# BLE.net
KiCad netlist of a schematic drawn in Altium Designer
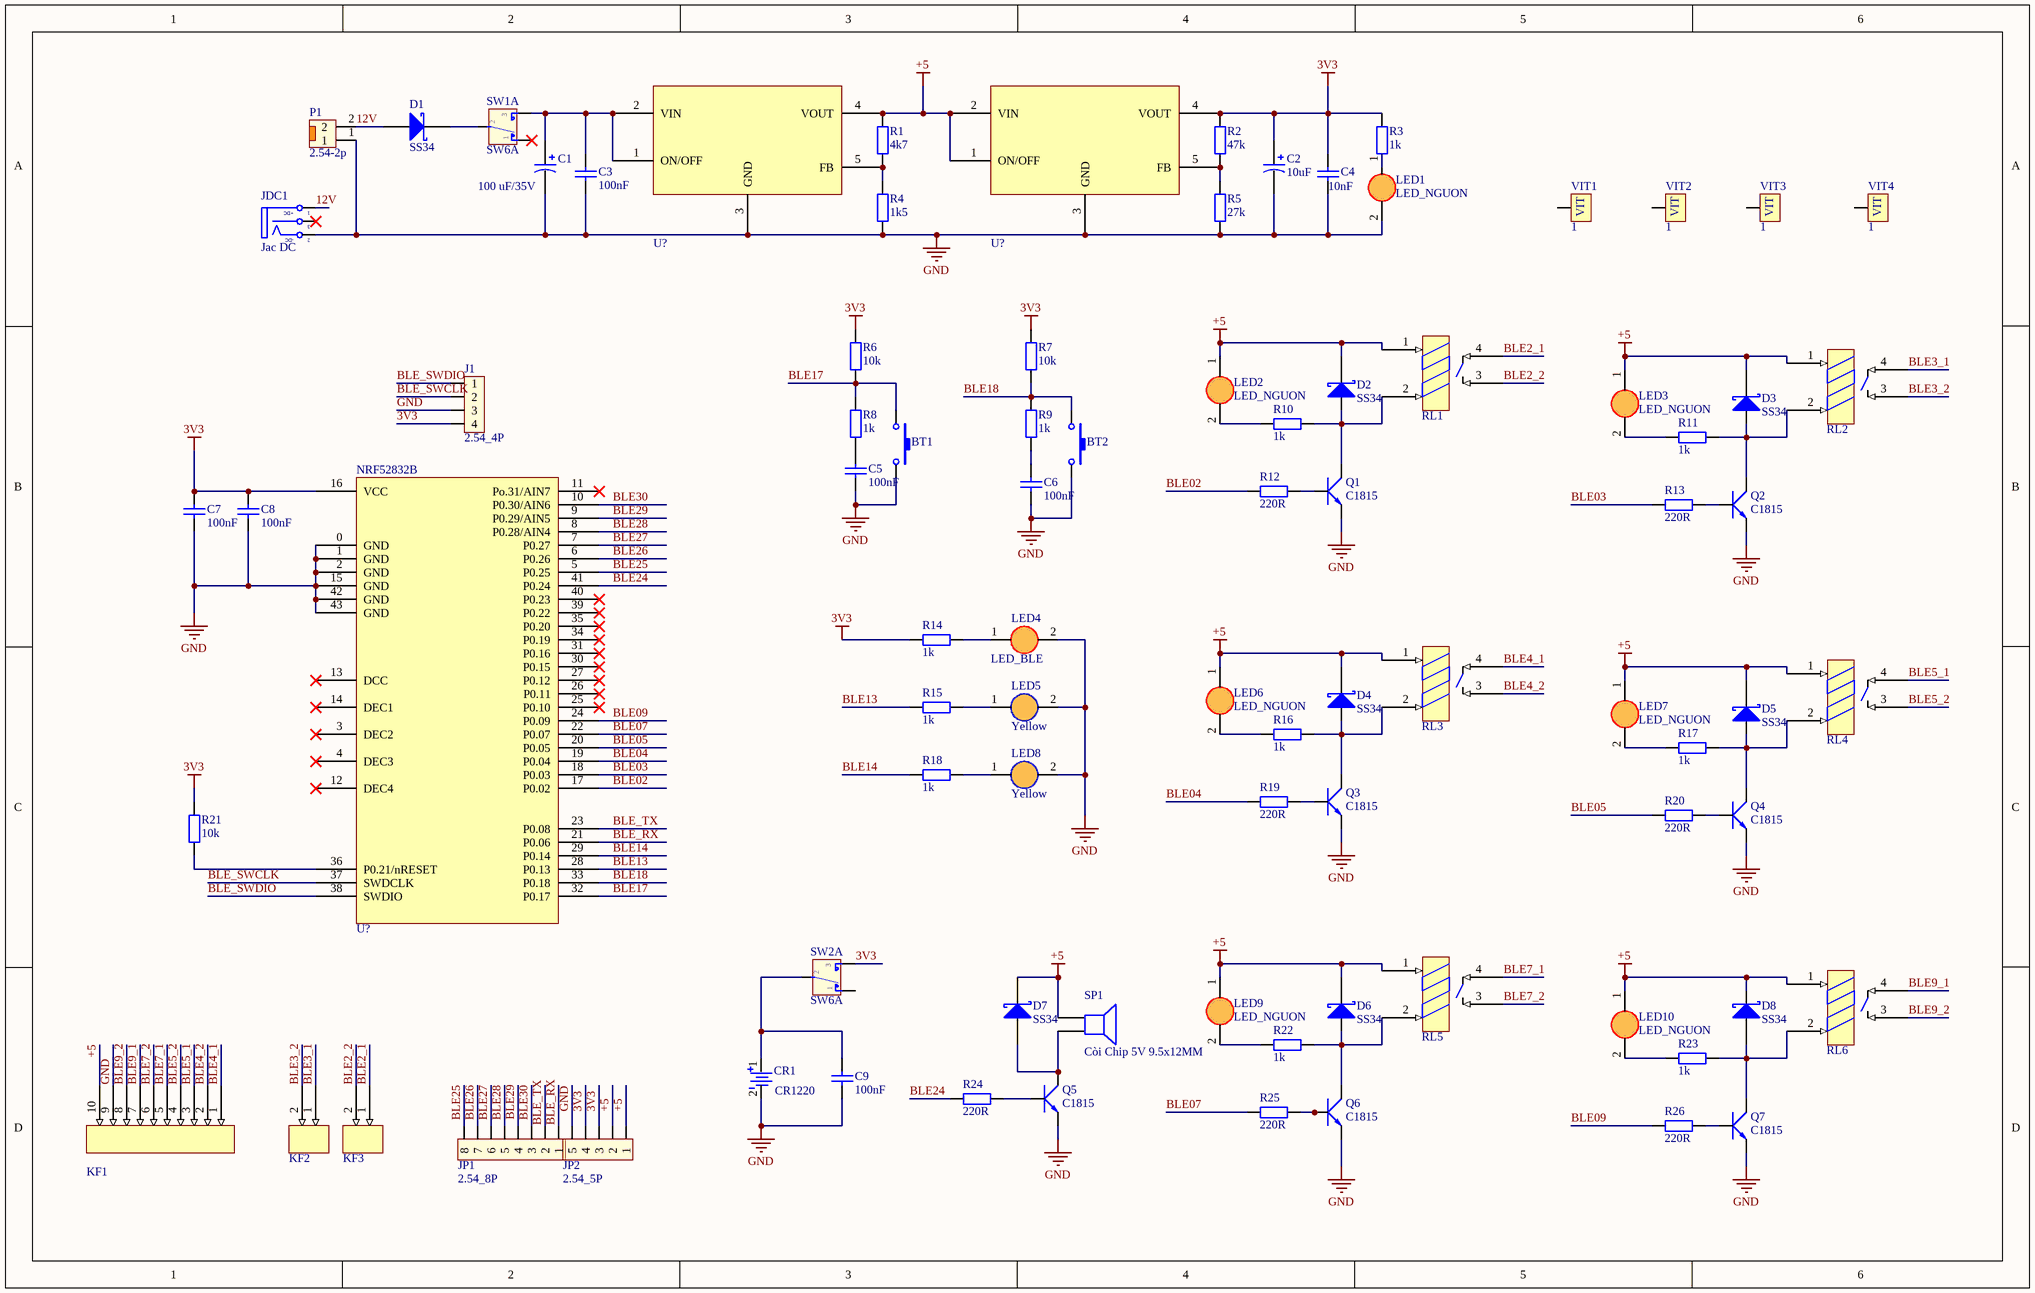
[diagram p0: BLE.SchDoc]

(export (version "E")
  (design (tool "Eeschema 10.0.6"))
  (components
    (comp (ref "BT1")
      (value "Nút Nhấn 2 Chân 3x6x2.5MM SMD")
      (footprint "Nut Nhan 2 Chan SMD_N")
      (description "Dán")
      (libsource (lib "NhomLib (1)") (part "Nut Nhan 2 Chan SMD"))
    )
    (comp (ref "BT2")
      (value "Nút Nhấn 2 Chân 3x6x2.5MM SMD")
      (footprint "Nut Nhan 2 Chan SMD_N")
      (description "Dán")
      (libsource (lib "NhomLib (1)") (part "Nut Nhan 2 Chan SMD"))
    )
    (comp (ref "C1")
      (value "100 uF/35V")
      (footprint "CAP_ALUM_SMD_100102_TYPE_G")
      (description "CAP ALUM 330uF 20% 35V SMD")
      (fields (field (name "MPN") "EEE-FK1C331P") (field (name "MFR") "Panasonic"))
      (libsource (lib "NhomLib (1)") (part "EEE-FK1C331P"))
    )
    (comp (ref "C2")
      (value "10uF")
      (footprint "CAP_ALUM_SMD_5054_TYPE_C")
      (description "CAP ALUM 33uF 20% 16V SMD")
      (fields (field (name "MPN") "EEE-FK1C330P") (field (name "MFR") "Panasonic"))
      (libsource (lib "NhomLib (1)") (part "EEE-FK1C330P"))
    )
    (comp (ref "C3")
      (value "100nF")
      (footprint "tu 0805")
      (description "Dán")
      (libsource (lib "NhomLib (1)") (part "Tu 0805 6.8nF 50V 10%"))
    )
    (comp (ref "C4")
      (value "10nF")
      (footprint "tu 0805")
      (description "Dán")
      (libsource (lib "NhomLib (1)") (part "Tu 0805 6.8nF 50V 10%"))
    )
    (comp (ref "C5")
      (value "100nF")
      (footprint "tu 0805")
      (description "Dán")
      (libsource (lib "NhomLib (1)") (part "Tu 0805 6.8nF 50V 10%"))
    )
    (comp (ref "C6")
      (value "100nF")
      (footprint "tu 0805")
      (description "Dán")
      (libsource (lib "NhomLib (1)") (part "Tu 0805 6.8nF 50V 10%"))
    )
    (comp (ref "C7")
      (value "100nF")
      (footprint "tu 0805")
      (description "Dán")
      (libsource (lib "NhomLib (1)") (part "Tu 0805 6.8nF 50V 10%"))
    )
    (comp (ref "C8")
      (value "100nF")
      (footprint "tu 0805")
      (description "Dán")
      (libsource (lib "NhomLib (1)") (part "Tu 0805 6.8nF 50V 10%"))
    )
    (comp (ref "C9")
      (value "100nF")
      (footprint "tu 0805")
      (description "Dán")
      (libsource (lib "NhomLib (1)") (part "Tu 0805 6.8nF 50V 10%"))
    )
    (comp (ref "CR1")
      (value "CR1220")
      (footprint "CR1220_HOLDER_SMD")
      (libsource (lib "VINH TRI") (part "CR1220"))
    )
    (comp (ref "D1")
      (value "SS34")
      (footprint "DIODE_DO214AC_SMA")
      (description "DIODE SCHOTTKY 40V 3A SMA")
      (libsource (lib "NhomLib (1)") (part "SS34"))
    )
    (comp (ref "D2")
      (value "SS34")
      (footprint "DIODE_DO214AC_SMA")
      (description "DIODE SCHOTTKY 40V 3A SMA")
      (libsource (lib "NhomLib (1)") (part "SS34"))
    )
    (comp (ref "D3")
      (value "SS34")
      (footprint "DIODE_DO214AC_SMA")
      (description "DIODE SCHOTTKY 40V 3A SMA")
      (libsource (lib "NhomLib (1)") (part "SS34"))
    )
    (comp (ref "D4")
      (value "SS34")
      (footprint "DIODE_DO214AC_SMA")
      (description "DIODE SCHOTTKY 40V 3A SMA")
      (libsource (lib "NhomLib (1)") (part "SS34"))
    )
    (comp (ref "D5")
      (value "SS34")
      (footprint "DIODE_DO214AC_SMA")
      (description "DIODE SCHOTTKY 40V 3A SMA")
      (libsource (lib "NhomLib (1)") (part "SS34"))
    )
    (comp (ref "D6")
      (value "SS34")
      (footprint "DIODE_DO214AC_SMA")
      (description "DIODE SCHOTTKY 40V 3A SMA")
      (libsource (lib "NhomLib (1)") (part "SS34"))
    )
    (comp (ref "D7")
      (value "SS34")
      (footprint "DIODE_DO214AC_SMA")
      (description "DIODE SCHOTTKY 40V 3A SMA")
      (libsource (lib "NhomLib (1)") (part "SS34"))
    )
    (comp (ref "D8")
      (value "SS34")
      (footprint "DIODE_DO214AC_SMA")
      (description "DIODE SCHOTTKY 40V 3A SMA")
      (libsource (lib "NhomLib (1)") (part "SS34"))
    )
    (comp (ref "J1")
      (value "2.54_4P")
      (footprint "jump don duc thang 2.54_4p")
      (description "Cắm")
      (libsource (lib "NhomLib (1)") (part "Jump Don Duc Thang 2.54_4P"))
    )
    (comp (ref "JDC1")
      (value "Jac DC")
      (footprint "DC-IN")
      (description "Jac DC input")
      (libsource (lib "NhomLib (1)") (part "DCIN"))
    )
    (comp (ref "JP1")
      (value "2.54_8P")
      (footprint "Jump Don Duc Thang 2.54_8p")
      (description "Cắm")
      (libsource (lib "NhomLib (1)") (part "Jump Don Duc 2.54_8P"))
    )
    (comp (ref "JP2")
      (value "2.54_5P")
      (footprint "jump don duc 2.54_5p")
      (description "Cắm")
      (libsource (lib "NhomLib (1)") (part "Jump Don Duc 2.54_5P"))
    )
    (comp (ref "KF1")
      (value "KF142R-10")
      (footprint "KF10")
      (description "KF142R-10P-5.08mm")
      (libsource (lib "B212H_01") (part "KF10"))
    )
    (comp (ref "KF2")
      (value "~")
      (footprint "KF2")
      (description "KF142R-2 5.08mm")
      (libsource (lib "B212H_01") (part "KF2"))
    )
    (comp (ref "KF3")
      (value "~")
      (footprint "KF2")
      (description "KF142R-2 5.08mm")
      (libsource (lib "B212H_01") (part "KF2"))
    )
    (comp (ref "LED1")
      (value "LED_NGUON")
      (footprint "led 0805")
      (description "Dán")
      (libsource (lib "NhomLib (1)") (part "Led 0805 Do"))
    )
    (comp (ref "LED2")
      (value "LED_NGUON")
      (footprint "led 0805")
      (description "Dán")
      (libsource (lib "NhomLib (1)") (part "Led 0805 Do"))
    )
    (comp (ref "LED3")
      (value "LED_NGUON")
      (footprint "led 0805")
      (description "Dán")
      (libsource (lib "NhomLib (1)") (part "Led 0805 Do"))
    )
    (comp (ref "LED4")
      (value "LED_BLE")
      (footprint "led 0805")
      (description "Dán")
      (libsource (lib "NhomLib (1)") (part "Led 0805 Do"))
    )
    (comp (ref "LED5")
      (value "Yellow")
      (footprint "led 0805")
      (description "Dán")
      (libsource (lib "NhomLib (1)") (part "Led 0805 Xanh Duong"))
    )
    (comp (ref "LED6")
      (value "LED_NGUON")
      (footprint "led 0805")
      (description "Dán")
      (libsource (lib "NhomLib (1)") (part "Led 0805 Do"))
    )
    (comp (ref "LED7")
      (value "LED_NGUON")
      (footprint "led 0805")
      (description "Dán")
      (libsource (lib "NhomLib (1)") (part "Led 0805 Do"))
    )
    (comp (ref "LED8")
      (value "Yellow")
      (footprint "led 0805")
      (description "Dán")
      (libsource (lib "NhomLib (1)") (part "Led 0805 Xanh Duong"))
    )
    (comp (ref "LED9")
      (value "LED_NGUON")
      (footprint "led 0805")
      (description "Dán")
      (libsource (lib "NhomLib (1)") (part "Led 0805 Do"))
    )
    (comp (ref "LED10")
      (value "LED_NGUON")
      (footprint "led 0805")
      (description "Dán")
      (libsource (lib "NhomLib (1)") (part "Led 0805 Do"))
    )
    (comp (ref "MIC1")
      (value "U?")
      (footprint "Mic5V")
      (description "3A")
      (libsource (lib "NodeMCU-ESP8266") (part "Mic5V"))
    )
    (comp (ref "MIC2")
      (value "U?")
      (footprint "Mic5V")
      (description "3A")
      (libsource (lib "NodeMCU-ESP8266") (part "Mic5V"))
    )
    (comp (ref "NRF52832") (value "U?") (footprint "NRF52832") (libsource (lib "NRF52832") (part "U?")))
    (comp (ref "P1")
      (value "2.54-2p")
      (footprint "Header Duc Thang 2P 2.54")
      (description "Cắm")
      (libsource (lib "NhomLib (1)") (part "Header 2.54-2p Duc Thang"))
    )
    (comp (ref "Q1")
      (value "C1815")
      (footprint "SOT23B")
      (description "NPN 600mW, ECB")
      (libsource (lib "syhaunguyen") (part "C1815"))
    )
    (comp (ref "Q2")
      (value "C1815")
      (footprint "SOT23B")
      (description "NPN 600mW, ECB")
      (libsource (lib "syhaunguyen") (part "C1815"))
    )
    (comp (ref "Q3")
      (value "C1815")
      (footprint "SOT23B")
      (description "NPN 600mW, ECB")
      (libsource (lib "syhaunguyen") (part "C1815"))
    )
    (comp (ref "Q4")
      (value "C1815")
      (footprint "SOT23B")
      (description "NPN 600mW, ECB")
      (libsource (lib "syhaunguyen") (part "C1815"))
    )
    (comp (ref "Q5")
      (value "C1815")
      (footprint "SOT23B")
      (description "NPN 600mW, ECB")
      (libsource (lib "syhaunguyen") (part "C1815"))
    )
    (comp (ref "Q6")
      (value "C1815")
      (footprint "SOT23B")
      (description "NPN 600mW, ECB")
      (libsource (lib "syhaunguyen") (part "C1815"))
    )
    (comp (ref "Q7")
      (value "C1815")
      (footprint "SOT23B")
      (description "NPN 600mW, ECB")
      (libsource (lib "syhaunguyen") (part "C1815"))
    )
    (comp (ref "R1")
      (value "4k7")
      (footprint "tro 0805")
      (description "Dán")
      (libsource (lib "NhomLib (1)") (part "Tro 0805 1% 10k"))
    )
    (comp (ref "R2")
      (value "47k")
      (footprint "tro 0805")
      (description "Dán")
      (libsource (lib "NhomLib (1)") (part "Tro 0805 1% 10k"))
    )
    (comp (ref "R3")
      (value "1k")
      (footprint "tro 0805")
      (description "Dán")
      (libsource (lib "NhomLib (1)") (part "Tro 0805 1% 10k"))
    )
    (comp (ref "R4")
      (value "1k5")
      (footprint "tro 0805")
      (description "Dán")
      (libsource (lib "NhomLib (1)") (part "Tro 0805 1% 10k"))
    )
    (comp (ref "R5")
      (value "27k")
      (footprint "tro 0805")
      (description "Dán")
      (libsource (lib "NhomLib (1)") (part "Tro 0805 1% 10k"))
    )
    (comp (ref "R6")
      (value "10k")
      (footprint "tro 0805")
      (description "Dán")
      (libsource (lib "NhomLib (1)") (part "Tro 0805 1% 10k"))
    )
    (comp (ref "R7")
      (value "10k")
      (footprint "tro 0805")
      (description "Dán")
      (libsource (lib "NhomLib (1)") (part "Tro 0805 1% 10k"))
    )
    (comp (ref "R8")
      (value "1k")
      (footprint "tro 0805")
      (description "Dán")
      (libsource (lib "NhomLib (1)") (part "Tro 0805 1% 10k"))
    )
    (comp (ref "R9")
      (value "1k")
      (footprint "tro 0805")
      (description "Dán")
      (libsource (lib "NhomLib (1)") (part "Tro 0805 1% 10k"))
    )
    (comp (ref "R10")
      (value "1k")
      (footprint "tro 0805")
      (description "Dán")
      (libsource (lib "NhomLib (1)") (part "Tro 0805 1% 10k"))
    )
    (comp (ref "R11")
      (value "1k")
      (footprint "tro 0805")
      (description "Dán")
      (libsource (lib "NhomLib (1)") (part "Tro 0805 1% 10k"))
    )
    (comp (ref "R12")
      (value "220R")
      (footprint "tro 0805")
      (description "Dán")
      (libsource (lib "NhomLib (1)") (part "Tro 0805 1% 10k"))
    )
    (comp (ref "R13")
      (value "220R")
      (footprint "tro 0805")
      (description "Dán")
      (libsource (lib "NhomLib (1)") (part "Tro 0805 1% 10k"))
    )
    (comp (ref "R14")
      (value "1k")
      (footprint "tro 0805")
      (description "Dán")
      (libsource (lib "NhomLib (1)") (part "Tro 0805 1% 10k"))
    )
    (comp (ref "R15")
      (value "1k")
      (footprint "tro 0805")
      (description "Dán")
      (libsource (lib "NhomLib (1)") (part "Tro 0805 1% 10k"))
    )
    (comp (ref "R16")
      (value "1k")
      (footprint "tro 0805")
      (description "Dán")
      (libsource (lib "NhomLib (1)") (part "Tro 0805 1% 10k"))
    )
    (comp (ref "R17")
      (value "1k")
      (footprint "tro 0805")
      (description "Dán")
      (libsource (lib "NhomLib (1)") (part "Tro 0805 1% 10k"))
    )
    (comp (ref "R18")
      (value "1k")
      (footprint "tro 0805")
      (description "Dán")
      (libsource (lib "NhomLib (1)") (part "Tro 0805 1% 10k"))
    )
    (comp (ref "R19")
      (value "220R")
      (footprint "tro 0805")
      (description "Dán")
      (libsource (lib "NhomLib (1)") (part "Tro 0805 1% 10k"))
    )
    (comp (ref "R20")
      (value "220R")
      (footprint "tro 0805")
      (description "Dán")
      (libsource (lib "NhomLib (1)") (part "Tro 0805 1% 10k"))
    )
    (comp (ref "R21")
      (value "10k")
      (footprint "tro 0805")
      (description "Dán")
      (libsource (lib "NhomLib (1)") (part "Tro 0805 1% 10k"))
    )
    (comp (ref "R22")
      (value "1k")
      (footprint "tro 0805")
      (description "Dán")
      (libsource (lib "NhomLib (1)") (part "Tro 0805 1% 10k"))
    )
    (comp (ref "R23")
      (value "1k")
      (footprint "tro 0805")
      (description "Dán")
      (libsource (lib "NhomLib (1)") (part "Tro 0805 1% 10k"))
    )
    (comp (ref "R24")
      (value "220R")
      (footprint "tro 0805")
      (description "Dán")
      (libsource (lib "NhomLib (1)") (part "Tro 0805 1% 10k"))
    )
    (comp (ref "R25")
      (value "220R")
      (footprint "tro 0805")
      (description "Dán")
      (libsource (lib "NhomLib (1)") (part "Tro 0805 1% 10k"))
    )
    (comp (ref "R26")
      (value "220R")
      (footprint "tro 0805")
      (description "Dán")
      (libsource (lib "NhomLib (1)") (part "Tro 0805 1% 10k"))
    )
    (comp (ref "RL1") (value "Relay-4") (footprint "Relay-4") (libsource (lib "B212H_01") (part "Relay-4")))
    (comp (ref "RL2") (value "Relay-4") (footprint "Relay-4") (libsource (lib "B212H_01") (part "Relay-4")))
    (comp (ref "RL3") (value "Relay-4") (footprint "Relay-4") (libsource (lib "B212H_01") (part "Relay-4")))
    (comp (ref "RL4") (value "Relay-4") (footprint "Relay-4") (libsource (lib "B212H_01") (part "Relay-4")))
    (comp (ref "RL5") (value "Relay-4") (footprint "Relay-4") (libsource (lib "B212H_01") (part "Relay-4")))
    (comp (ref "RL6") (value "Relay-4") (footprint "Relay-4") (libsource (lib "B212H_01") (part "Relay-4")))
    (comp (ref "SP1")
      (value "Còi Chip 5V 9.5x12MM")
      (footprint "SPEAKER")
      (description "Cắm")
      (libsource (lib "NhomLib (1)") (part "Coi Chip 5V"))
    )
    (comp (ref "SW1")
      (value "SW6A")
      (footprint "SW6")
      (description "SW-DTDP - 6 Pin")
      (libsource (lib "NhomLib (1)") (part "SW6A"))
    )
    (comp (ref "SW2")
      (value "SW6A")
      (footprint "SW6")
      (description "SW-DTDP - 6 Pin")
      (libsource (lib "NhomLib (1)") (part "SW6A"))
    )
    (comp (ref "VIT1")
      (value "1")
      (footprint "VIT")
      (description "Oc Vit")
      (libsource (lib "NhomLib (1)") (part "VIT"))
    )
    (comp (ref "VIT2")
      (value "1")
      (footprint "VIT")
      (description "Oc Vit")
      (libsource (lib "NhomLib (1)") (part "VIT"))
    )
    (comp (ref "VIT3")
      (value "1")
      (footprint "VIT")
      (description "Oc Vit")
      (libsource (lib "NhomLib (1)") (part "VIT"))
    )
    (comp (ref "VIT4")
      (value "1")
      (footprint "VIT")
      (description "Oc Vit")
      (libsource (lib "NhomLib (1)") (part "VIT"))
    )
  )
  (nets
    (net (code "1") (name "+5") (class "Default")
      (node (ref "D2") (pin "2") (pinfunction "K_2") (pintype "passive"))
      (node (ref "D3") (pin "2") (pinfunction "K_2") (pintype "passive"))
      (node (ref "D4") (pin "2") (pinfunction "K_2") (pintype "passive"))
      (node (ref "D5") (pin "2") (pinfunction "K_2") (pintype "passive"))
      (node (ref "D6") (pin "2") (pinfunction "K_2") (pintype "passive"))
      (node (ref "D7") (pin "2") (pinfunction "K_2") (pintype "passive"))
      (node (ref "D8") (pin "2") (pinfunction "K_2") (pintype "passive"))
      (node (ref "JP2") (pin "1") (pinfunction "1_1") (pintype "passive"))
      (node (ref "JP2") (pin "2") (pinfunction "2_2") (pintype "passive"))
      (node (ref "KF1") (pin "10") (pintype "input"))
      (node (ref "LED10") (pin "1") (pinfunction "A_1") (pintype "passive"))
      (node (ref "LED2") (pin "1") (pinfunction "A_1") (pintype "passive"))
      (node (ref "LED3") (pin "1") (pinfunction "A_1") (pintype "passive"))
      (node (ref "LED6") (pin "1") (pinfunction "A_1") (pintype "passive"))
      (node (ref "LED7") (pin "1") (pinfunction "A_1") (pintype "passive"))
      (node (ref "LED9") (pin "1") (pinfunction "A_1") (pintype "passive"))
      (node (ref "MIC1") (pin "4") (pinfunction "VOUT_4") (pintype "passive"))
      (node (ref "MIC2") (pin "1") (pinfunction "ON/OFF_1") (pintype "passive"))
      (node (ref "MIC2") (pin "2") (pinfunction "VIN_2") (pintype "passive"))
      (node (ref "R1") (pin "1") (pinfunction "1_1") (pintype "passive"))
      (node (ref "RL1") (pin "1") (pintype "input"))
      (node (ref "RL2") (pin "1") (pintype "input"))
      (node (ref "RL3") (pin "1") (pintype "input"))
      (node (ref "RL4") (pin "1") (pintype "input"))
      (node (ref "RL5") (pin "1") (pintype "input"))
      (node (ref "RL6") (pin "1") (pintype "input"))
      (node (ref "SP1") (pin "1") (pinfunction "1_1") (pintype "passive"))
    )
    (net (code "2") (name "/12V") (class "Default")
      (node (ref "D1") (pin "1") (pinfunction "A_1") (pintype "passive"))
      (node (ref "JDC1") (pin "1") (pinfunction "T_1") (pintype "passive"))
      (node (ref "P1") (pin "2") (pinfunction "2_2") (pintype "passive"))
    )
    (net (code "3") (name "/BLE02") (class "Default")
      (node (ref "NRF52832") (pin "17") (pinfunction "P0.02_17") (pintype "passive"))
      (node (ref "R12") (pin "2") (pinfunction "2_2") (pintype "passive"))
    )
    (net (code "4") (name "/BLE2_1") (class "Default")
      (node (ref "KF3") (pin "1") (pintype "input"))
      (node (ref "RL1") (pin "4") (pintype "input"))
    )
    (net (code "5") (name "/BLE2_2") (class "Default")
      (node (ref "KF3") (pin "2") (pintype "input"))
      (node (ref "RL1") (pin "3") (pintype "input"))
    )
    (net (code "6") (name "/BLE03") (class "Default")
      (node (ref "NRF52832") (pin "18") (pinfunction "P0.03_18") (pintype "passive"))
      (node (ref "R13") (pin "2") (pinfunction "2_2") (pintype "passive"))
    )
    (net (code "7") (name "/BLE3_1") (class "Default")
      (node (ref "KF2") (pin "1") (pintype "input"))
      (node (ref "RL2") (pin "4") (pintype "input"))
    )
    (net (code "8") (name "/BLE3_2") (class "Default")
      (node (ref "KF2") (pin "2") (pintype "input"))
      (node (ref "RL2") (pin "3") (pintype "input"))
    )
    (net (code "9") (name "/BLE04") (class "Default")
      (node (ref "NRF52832") (pin "19") (pinfunction "P0.04_19") (pintype "passive"))
      (node (ref "R19") (pin "2") (pinfunction "2_2") (pintype "passive"))
    )
    (net (code "10") (name "/BLE4_1") (class "Default")
      (node (ref "KF1") (pin "1") (pintype "input"))
      (node (ref "RL3") (pin "4") (pintype "input"))
    )
    (net (code "11") (name "/BLE4_2") (class "Default")
      (node (ref "KF1") (pin "2") (pintype "input"))
      (node (ref "RL3") (pin "3") (pintype "input"))
    )
    (net (code "12") (name "/BLE05") (class "Default")
      (node (ref "NRF52832") (pin "20") (pinfunction "P0.05_20") (pintype "passive"))
      (node (ref "R20") (pin "2") (pinfunction "2_2") (pintype "passive"))
    )
    (net (code "13") (name "/BLE5_1") (class "Default")
      (node (ref "KF1") (pin "3") (pintype "input"))
      (node (ref "RL4") (pin "4") (pintype "input"))
    )
    (net (code "14") (name "/BLE5_2") (class "Default")
      (node (ref "KF1") (pin "4") (pintype "input"))
      (node (ref "RL4") (pin "3") (pintype "input"))
    )
    (net (code "15") (name "/BLE07") (class "Default")
      (node (ref "NRF52832") (pin "22") (pinfunction "P0.07_22") (pintype "passive"))
      (node (ref "R25") (pin "2") (pinfunction "2_2") (pintype "passive"))
    )
    (net (code "16") (name "/BLE7_1") (class "Default")
      (node (ref "KF1") (pin "5") (pintype "input"))
      (node (ref "RL5") (pin "4") (pintype "input"))
    )
    (net (code "17") (name "/BLE7_2") (class "Default")
      (node (ref "KF1") (pin "6") (pintype "input"))
      (node (ref "RL5") (pin "3") (pintype "input"))
    )
    (net (code "18") (name "/BLE09") (class "Default")
      (node (ref "NRF52832") (pin "24") (pinfunction "P0.09_24") (pintype "passive"))
      (node (ref "R26") (pin "2") (pinfunction "2_2") (pintype "passive"))
    )
    (net (code "19") (name "/BLE9_1") (class "Default")
      (node (ref "KF1") (pin "7") (pintype "input"))
      (node (ref "RL6") (pin "4") (pintype "input"))
    )
    (net (code "20") (name "/BLE9_2") (class "Default")
      (node (ref "KF1") (pin "8") (pintype "input"))
      (node (ref "RL6") (pin "3") (pintype "input"))
    )
    (net (code "21") (name "/BLE13") (class "Default")
      (node (ref "NRF52832") (pin "28") (pinfunction "P0.13_28") (pintype "passive"))
      (node (ref "R15") (pin "2") (pinfunction "2_2") (pintype "passive"))
    )
    (net (code "22") (name "/BLE14") (class "Default")
      (node (ref "NRF52832") (pin "29") (pinfunction "P0.14_29") (pintype "passive"))
      (node (ref "R18") (pin "2") (pinfunction "2_2") (pintype "passive"))
    )
    (net (code "23") (name "/BLE17") (class "Default")
      (node (ref "BT1") (pin "1") (pinfunction "1_1") (pintype "passive"))
      (node (ref "NRF52832") (pin "32") (pinfunction "P0.17_32") (pintype "passive"))
      (node (ref "R6") (pin "2") (pinfunction "2_2") (pintype "passive"))
      (node (ref "R8") (pin "2") (pinfunction "2_2") (pintype "passive"))
    )
    (net (code "24") (name "/BLE18") (class "Default")
      (node (ref "BT2") (pin "1") (pinfunction "1_1") (pintype "passive"))
      (node (ref "NRF52832") (pin "33") (pinfunction "P0.18_33") (pintype "passive"))
      (node (ref "R7") (pin "2") (pinfunction "2_2") (pintype "passive"))
      (node (ref "R9") (pin "2") (pinfunction "2_2") (pintype "passive"))
    )
    (net (code "25") (name "/BLE24") (class "Default")
      (node (ref "NRF52832") (pin "41") (pinfunction "P0.24_41") (pintype "passive"))
      (node (ref "R24") (pin "2") (pinfunction "2_2") (pintype "passive"))
    )
    (net (code "26") (name "/BLE25") (class "Default")
      (node (ref "JP1") (pin "8") (pinfunction "8_8") (pintype "passive"))
      (node (ref "NRF52832") (pin "5") (pinfunction "P0.25_5") (pintype "passive"))
    )
    (net (code "27") (name "/BLE26") (class "Default")
      (node (ref "JP1") (pin "7") (pinfunction "7_7") (pintype "passive"))
      (node (ref "NRF52832") (pin "6") (pinfunction "P0.26_6") (pintype "passive"))
    )
    (net (code "28") (name "/BLE27") (class "Default")
      (node (ref "JP1") (pin "6") (pinfunction "6_6") (pintype "passive"))
      (node (ref "NRF52832") (pin "7") (pinfunction "P0.27_7") (pintype "passive"))
    )
    (net (code "29") (name "/BLE28") (class "Default")
      (node (ref "JP1") (pin "5") (pinfunction "5_5") (pintype "passive"))
      (node (ref "NRF52832") (pin "8") (pinfunction "P0.28/AIN4_8") (pintype "passive"))
    )
    (net (code "30") (name "/BLE29") (class "Default")
      (node (ref "JP1") (pin "4") (pinfunction "4_4") (pintype "passive"))
      (node (ref "NRF52832") (pin "9") (pinfunction "P0.29/AIN5_9") (pintype "passive"))
    )
    (net (code "31") (name "/BLE30") (class "Default")
      (node (ref "JP1") (pin "3") (pinfunction "3_3") (pintype "passive"))
      (node (ref "NRF52832") (pin "10") (pinfunction "P0.30/AIN6_10") (pintype "passive"))
    )
    (net (code "32") (name "/BLE_RX") (class "Default")
      (node (ref "JP1") (pin "1") (pinfunction "1_1") (pintype "passive"))
      (node (ref "NRF52832") (pin "21") (pinfunction "P0.06_21") (pintype "passive"))
    )
    (net (code "33") (name "/BLE_SWCLK") (class "Default")
      (node (ref "J1") (pin "2") (pinfunction "2_2") (pintype "passive"))
      (node (ref "NRF52832") (pin "37") (pinfunction "SWDCLK_37") (pintype "passive"))
    )
    (net (code "34") (name "/BLE_SWDIO") (class "Default")
      (node (ref "J1") (pin "1") (pinfunction "1_1") (pintype "passive"))
      (node (ref "NRF52832") (pin "38") (pinfunction "SWDIO_38") (pintype "passive"))
    )
    (net (code "35") (name "/BLE_TX") (class "Default")
      (node (ref "JP1") (pin "2") (pinfunction "2_2") (pintype "passive"))
      (node (ref "NRF52832") (pin "23") (pinfunction "P0.08_23") (pintype "passive"))
    )
    (net (code "36") (name "3V3") (class "Default")
      (node (ref "C2") (pin "1") (pinfunction "1_1") (pintype "passive"))
      (node (ref "C4") (pin "1") (pinfunction "1_1") (pintype "passive"))
      (node (ref "C7") (pin "1") (pinfunction "1_1") (pintype "passive"))
      (node (ref "C8") (pin "1") (pinfunction "1_1") (pintype "passive"))
      (node (ref "J1") (pin "4") (pinfunction "4_4") (pintype "passive"))
      (node (ref "JP2") (pin "3") (pinfunction "3_3") (pintype "passive"))
      (node (ref "JP2") (pin "4") (pinfunction "4_4") (pintype "passive"))
      (node (ref "MIC2") (pin "4") (pinfunction "VOUT_4") (pintype "passive"))
      (node (ref "NRF52832") (pin "16") (pinfunction "VCC_16") (pintype "passive"))
      (node (ref "R14") (pin "2") (pinfunction "2_2") (pintype "passive"))
      (node (ref "R2") (pin "1") (pinfunction "1_1") (pintype "passive"))
      (node (ref "R21") (pin "1") (pinfunction "1_1") (pintype "passive"))
      (node (ref "R3") (pin "2") (pinfunction "2_2") (pintype "passive"))
      (node (ref "R6") (pin "1") (pinfunction "1_1") (pintype "passive"))
      (node (ref "R7") (pin "1") (pinfunction "1_1") (pintype "passive"))
      (node (ref "SW2") (pin "3") (pinfunction "3_3") (pintype "passive"))
    )
    (net (code "37") (name "GND") (class "Default")
      (node (ref "BT1") (pin "2") (pinfunction "2_2") (pintype "passive"))
      (node (ref "BT2") (pin "2") (pinfunction "2_2") (pintype "passive"))
      (node (ref "C1") (pin "2") (pinfunction "2_2") (pintype "passive"))
      (node (ref "C2") (pin "2") (pinfunction "2_2") (pintype "passive"))
      (node (ref "C3") (pin "2") (pinfunction "2_2") (pintype "passive"))
      (node (ref "C4") (pin "2") (pinfunction "2_2") (pintype "passive"))
      (node (ref "C5") (pin "2") (pinfunction "2_2") (pintype "passive"))
      (node (ref "C6") (pin "2") (pinfunction "2_2") (pintype "passive"))
      (node (ref "C7") (pin "2") (pinfunction "2_2") (pintype "passive"))
      (node (ref "C8") (pin "2") (pinfunction "2_2") (pintype "passive"))
      (node (ref "C9") (pin "2") (pinfunction "2_2") (pintype "passive"))
      (node (ref "CR1") (pin "2") (pinfunction "-_2") (pintype "passive"))
      (node (ref "J1") (pin "3") (pinfunction "3_3") (pintype "passive"))
      (node (ref "JDC1") (pin "2") (pinfunction "TN_2") (pintype "passive"))
      (node (ref "JP2") (pin "5") (pinfunction "5_5") (pintype "passive"))
      (node (ref "KF1") (pin "9") (pintype "input"))
      (node (ref "LED1") (pin "2") (pinfunction "K_2") (pintype "passive"))
      (node (ref "LED4") (pin "2") (pinfunction "K_2") (pintype "passive"))
      (node (ref "LED5") (pin "2") (pinfunction "K_2") (pintype "passive"))
      (node (ref "LED8") (pin "2") (pinfunction "K_2") (pintype "passive"))
      (node (ref "MIC1") (pin "3") (pinfunction "GND_3") (pintype "passive"))
      (node (ref "MIC2") (pin "3") (pinfunction "GND_3") (pintype "passive"))
      (node (ref "NRF52832") (pin "0") (pinfunction "GND_0") (pintype "passive"))
      (node (ref "NRF52832") (pin "1") (pinfunction "GND_1") (pintype "passive"))
      (node (ref "NRF52832") (pin "15") (pinfunction "GND_15") (pintype "passive"))
      (node (ref "NRF52832") (pin "2") (pinfunction "GND_2") (pintype "passive"))
      (node (ref "NRF52832") (pin "42") (pinfunction "GND_42") (pintype "passive"))
      (node (ref "NRF52832") (pin "43") (pinfunction "GND_43") (pintype "passive"))
      (node (ref "P1") (pin "1") (pinfunction "1_1") (pintype "passive"))
      (node (ref "Q1") (pin "1") (pinfunction "E_1") (pintype "passive"))
      (node (ref "Q2") (pin "1") (pinfunction "E_1") (pintype "passive"))
      (node (ref "Q3") (pin "1") (pinfunction "E_1") (pintype "passive"))
      (node (ref "Q4") (pin "1") (pinfunction "E_1") (pintype "passive"))
      (node (ref "Q5") (pin "1") (pinfunction "E_1") (pintype "passive"))
      (node (ref "Q6") (pin "1") (pinfunction "E_1") (pintype "passive"))
      (node (ref "Q7") (pin "1") (pinfunction "E_1") (pintype "passive"))
      (node (ref "R4") (pin "2") (pinfunction "2_2") (pintype "passive"))
      (node (ref "R5") (pin "2") (pinfunction "2_2") (pintype "passive"))
    )
    (net (code "38") (name "Net-(C5-Pad1)") (class "Default")
      (node (ref "C5") (pin "1") (pinfunction "1_1") (pintype "passive"))
      (node (ref "R8") (pin "1") (pinfunction "1_1") (pintype "passive"))
    )
    (net (code "39") (name "Net-(C6-Pad1)") (class "Default")
      (node (ref "C6") (pin "1") (pinfunction "1_1") (pintype "passive"))
      (node (ref "R9") (pin "1") (pinfunction "1_1") (pintype "passive"))
    )
    (net (code "40") (name "Net-(CR1-+)") (class "Default")
      (node (ref "C9") (pin "1") (pinfunction "1_1") (pintype "passive"))
      (node (ref "CR1") (pin "1") (pinfunction "+_1") (pintype "passive"))
      (node (ref "SW2") (pin "2") (pinfunction "2_2") (pintype "passive"))
    )
    (net (code "41") (name "Net-(D1-K)") (class "Default")
      (node (ref "D1") (pin "2") (pinfunction "K_2") (pintype "passive"))
      (node (ref "SW1") (pin "2") (pinfunction "2_2") (pintype "passive"))
    )
    (net (code "42") (name "Net-(D2-A)") (class "Default")
      (node (ref "D2") (pin "1") (pinfunction "A_1") (pintype "passive"))
      (node (ref "Q1") (pin "2") (pinfunction "C_2") (pintype "passive"))
      (node (ref "R10") (pin "1") (pinfunction "1_1") (pintype "passive"))
      (node (ref "RL1") (pin "2") (pintype "input"))
    )
    (net (code "43") (name "Net-(D3-A)") (class "Default")
      (node (ref "D3") (pin "1") (pinfunction "A_1") (pintype "passive"))
      (node (ref "Q2") (pin "2") (pinfunction "C_2") (pintype "passive"))
      (node (ref "R11") (pin "1") (pinfunction "1_1") (pintype "passive"))
      (node (ref "RL2") (pin "2") (pintype "input"))
    )
    (net (code "44") (name "Net-(D4-A)") (class "Default")
      (node (ref "D4") (pin "1") (pinfunction "A_1") (pintype "passive"))
      (node (ref "Q3") (pin "2") (pinfunction "C_2") (pintype "passive"))
      (node (ref "R16") (pin "1") (pinfunction "1_1") (pintype "passive"))
      (node (ref "RL3") (pin "2") (pintype "input"))
    )
    (net (code "45") (name "Net-(D5-A)") (class "Default")
      (node (ref "D5") (pin "1") (pinfunction "A_1") (pintype "passive"))
      (node (ref "Q4") (pin "2") (pinfunction "C_2") (pintype "passive"))
      (node (ref "R17") (pin "1") (pinfunction "1_1") (pintype "passive"))
      (node (ref "RL4") (pin "2") (pintype "input"))
    )
    (net (code "46") (name "Net-(D6-A)") (class "Default")
      (node (ref "D6") (pin "1") (pinfunction "A_1") (pintype "passive"))
      (node (ref "Q6") (pin "2") (pinfunction "C_2") (pintype "passive"))
      (node (ref "R22") (pin "1") (pinfunction "1_1") (pintype "passive"))
      (node (ref "RL5") (pin "2") (pintype "input"))
    )
    (net (code "47") (name "Net-(D7-A)") (class "Default")
      (node (ref "D7") (pin "1") (pinfunction "A_1") (pintype "passive"))
      (node (ref "Q5") (pin "2") (pinfunction "C_2") (pintype "passive"))
      (node (ref "SP1") (pin "2") (pinfunction "2_2") (pintype "passive"))
    )
    (net (code "48") (name "Net-(D8-A)") (class "Default")
      (node (ref "D8") (pin "1") (pinfunction "A_1") (pintype "passive"))
      (node (ref "Q7") (pin "2") (pinfunction "C_2") (pintype "passive"))
      (node (ref "R23") (pin "1") (pinfunction "1_1") (pintype "passive"))
      (node (ref "RL6") (pin "2") (pintype "input"))
    )
    (net (code "49") (name "Net-(LED1-A)") (class "Default")
      (node (ref "LED1") (pin "1") (pinfunction "A_1") (pintype "passive"))
      (node (ref "R3") (pin "1") (pinfunction "1_1") (pintype "passive"))
    )
    (net (code "50") (name "Net-(LED2-K)") (class "Default")
      (node (ref "LED2") (pin "2") (pinfunction "K_2") (pintype "passive"))
      (node (ref "R10") (pin "2") (pinfunction "2_2") (pintype "passive"))
    )
    (net (code "51") (name "Net-(LED3-K)") (class "Default")
      (node (ref "LED3") (pin "2") (pinfunction "K_2") (pintype "passive"))
      (node (ref "R11") (pin "2") (pinfunction "2_2") (pintype "passive"))
    )
    (net (code "52") (name "Net-(LED4-A)") (class "Default")
      (node (ref "LED4") (pin "1") (pinfunction "A_1") (pintype "passive"))
      (node (ref "R14") (pin "1") (pinfunction "1_1") (pintype "passive"))
    )
    (net (code "53") (name "Net-(LED5-A)") (class "Default")
      (node (ref "LED5") (pin "1") (pinfunction "A_1") (pintype "passive"))
      (node (ref "R15") (pin "1") (pinfunction "1_1") (pintype "passive"))
    )
    (net (code "54") (name "Net-(LED6-K)") (class "Default")
      (node (ref "LED6") (pin "2") (pinfunction "K_2") (pintype "passive"))
      (node (ref "R16") (pin "2") (pinfunction "2_2") (pintype "passive"))
    )
    (net (code "55") (name "Net-(LED7-K)") (class "Default")
      (node (ref "LED7") (pin "2") (pinfunction "K_2") (pintype "passive"))
      (node (ref "R17") (pin "2") (pinfunction "2_2") (pintype "passive"))
    )
    (net (code "56") (name "Net-(LED8-A)") (class "Default")
      (node (ref "LED8") (pin "1") (pinfunction "A_1") (pintype "passive"))
      (node (ref "R18") (pin "1") (pinfunction "1_1") (pintype "passive"))
    )
    (net (code "57") (name "Net-(LED9-K)") (class "Default")
      (node (ref "LED9") (pin "2") (pinfunction "K_2") (pintype "passive"))
      (node (ref "R22") (pin "2") (pinfunction "2_2") (pintype "passive"))
    )
    (net (code "58") (name "Net-(LED10-K)") (class "Default")
      (node (ref "LED10") (pin "2") (pinfunction "K_2") (pintype "passive"))
      (node (ref "R23") (pin "2") (pinfunction "2_2") (pintype "passive"))
    )
    (net (code "59") (name "Net-(MIC1-FB)") (class "Default")
      (node (ref "MIC1") (pin "5") (pinfunction "FB_5") (pintype "passive"))
      (node (ref "R1") (pin "2") (pinfunction "2_2") (pintype "passive"))
      (node (ref "R4") (pin "1") (pinfunction "1_1") (pintype "passive"))
    )
    (net (code "60") (name "Net-(MIC1-ON{slash}OFF)") (class "Default")
      (node (ref "C1") (pin "1") (pinfunction "1_1") (pintype "passive"))
      (node (ref "C3") (pin "1") (pinfunction "1_1") (pintype "passive"))
      (node (ref "MIC1") (pin "1") (pinfunction "ON/OFF_1") (pintype "passive"))
      (node (ref "MIC1") (pin "2") (pinfunction "VIN_2") (pintype "passive"))
      (node (ref "SW1") (pin "3") (pinfunction "3_3") (pintype "passive"))
    )
    (net (code "61") (name "Net-(MIC2-FB)") (class "Default")
      (node (ref "MIC2") (pin "5") (pinfunction "FB_5") (pintype "passive"))
      (node (ref "R2") (pin "2") (pinfunction "2_2") (pintype "passive"))
      (node (ref "R5") (pin "1") (pinfunction "1_1") (pintype "passive"))
    )
    (net (code "62") (name "Net-(NRF52832B-P0.21{slash}nRESET)") (class "Default")
      (node (ref "NRF52832") (pin "36") (pinfunction "P0.21/nRESET_36") (pintype "passive"))
      (node (ref "R21") (pin "2") (pinfunction "2_2") (pintype "passive"))
    )
    (net (code "63") (name "Net-(Q1-B)") (class "Default")
      (node (ref "Q1") (pin "3") (pinfunction "B_3") (pintype "passive"))
      (node (ref "R12") (pin "1") (pinfunction "1_1") (pintype "passive"))
    )
    (net (code "64") (name "Net-(Q2-B)") (class "Default")
      (node (ref "Q2") (pin "3") (pinfunction "B_3") (pintype "passive"))
      (node (ref "R13") (pin "1") (pinfunction "1_1") (pintype "passive"))
    )
    (net (code "65") (name "Net-(Q3-B)") (class "Default")
      (node (ref "Q3") (pin "3") (pinfunction "B_3") (pintype "passive"))
      (node (ref "R19") (pin "1") (pinfunction "1_1") (pintype "passive"))
    )
    (net (code "66") (name "Net-(Q4-B)") (class "Default")
      (node (ref "Q4") (pin "3") (pinfunction "B_3") (pintype "passive"))
      (node (ref "R20") (pin "1") (pinfunction "1_1") (pintype "passive"))
    )
    (net (code "67") (name "Net-(Q5-B)") (class "Default")
      (node (ref "Q5") (pin "3") (pinfunction "B_3") (pintype "passive"))
      (node (ref "R24") (pin "1") (pinfunction "1_1") (pintype "passive"))
    )
    (net (code "68") (name "Net-(Q6-B)") (class "Default")
      (node (ref "Q6") (pin "3") (pinfunction "B_3") (pintype "passive"))
      (node (ref "R25") (pin "1") (pinfunction "1_1") (pintype "passive"))
    )
    (net (code "69") (name "Net-(Q7-B)") (class "Default")
      (node (ref "Q7") (pin "3") (pinfunction "B_3") (pintype "passive"))
      (node (ref "R26") (pin "1") (pinfunction "1_1") (pintype "passive"))
    )
    (net (code "70") (name "unconnected-(JDC1-S-Pad3)") (class "Default")
      (node (ref "JDC1") (pin "3") (pinfunction "S_3") (pintype "power_in+no_connect"))
    )
    (net (code "71") (name "unconnected-(NRF52832B-DCC-Pad13)") (class "Default")
      (node (ref "NRF52832") (pin "13") (pinfunction "DCC_13") (pintype "passive+no_connect"))
    )
    (net (code "72") (name "unconnected-(NRF52832B-DEC1-Pad14)") (class "Default")
      (node (ref "NRF52832") (pin "14") (pinfunction "DEC1_14") (pintype "passive+no_connect"))
    )
    (net (code "73") (name "unconnected-(NRF52832B-DEC2-Pad3)") (class "Default")
      (node (ref "NRF52832") (pin "3") (pinfunction "DEC2_3") (pintype "passive+no_connect"))
    )
    (net (code "74") (name "unconnected-(NRF52832B-DEC3-Pad4)") (class "Default")
      (node (ref "NRF52832") (pin "4") (pinfunction "DEC3_4") (pintype "passive+no_connect"))
    )
    (net (code "75") (name "unconnected-(NRF52832B-DEC4-Pad12)") (class "Default")
      (node (ref "NRF52832") (pin "12") (pinfunction "DEC4_12") (pintype "passive+no_connect"))
    )
    (net (code "76") (name "unconnected-(NRF52832B-P0.10-Pad25)") (class "Default")
      (node (ref "NRF52832") (pin "25") (pinfunction "P0.10_25") (pintype "passive+no_connect"))
    )
    (net (code "77") (name "unconnected-(NRF52832B-P0.11-Pad26)") (class "Default")
      (node (ref "NRF52832") (pin "26") (pinfunction "P0.11_26") (pintype "passive+no_connect"))
    )
    (net (code "78") (name "unconnected-(NRF52832B-P0.12-Pad27)") (class "Default")
      (node (ref "NRF52832") (pin "27") (pinfunction "P0.12_27") (pintype "passive+no_connect"))
    )
    (net (code "79") (name "unconnected-(NRF52832B-P0.15-Pad30)") (class "Default")
      (node (ref "NRF52832") (pin "30") (pinfunction "P0.15_30") (pintype "passive+no_connect"))
    )
    (net (code "80") (name "unconnected-(NRF52832B-P0.16-Pad31)") (class "Default")
      (node (ref "NRF52832") (pin "31") (pinfunction "P0.16_31") (pintype "passive+no_connect"))
    )
    (net (code "81") (name "unconnected-(NRF52832B-P0.19-Pad34)") (class "Default")
      (node (ref "NRF52832") (pin "34") (pinfunction "P0.19_34") (pintype "passive+no_connect"))
    )
    (net (code "82") (name "unconnected-(NRF52832B-P0.20-Pad35)") (class "Default")
      (node (ref "NRF52832") (pin "35") (pinfunction "P0.20_35") (pintype "passive+no_connect"))
    )
    (net (code "83") (name "unconnected-(NRF52832B-P0.22-Pad39)") (class "Default")
      (node (ref "NRF52832") (pin "39") (pinfunction "P0.22_39") (pintype "passive+no_connect"))
    )
    (net (code "84") (name "unconnected-(NRF52832B-P0.23-Pad40)") (class "Default")
      (node (ref "NRF52832") (pin "40") (pinfunction "P0.23_40") (pintype "passive+no_connect"))
    )
    (net (code "85") (name "unconnected-(NRF52832B-Po.31{slash}AIN7-Pad11)") (class "Default")
      (node (ref "NRF52832") (pin "11") (pinfunction "Po.31/AIN7_11") (pintype "passive+no_connect"))
    )
    (net (code "86") (name "unconnected-(SW1-Pad1)") (class "Default")
      (node (ref "SW1") (pin "1") (pinfunction "1_1") (pintype "passive+no_connect"))
    )
    (net (code "87") (name "unconnected-(SW2-Pad1)") (class "Default")
      (node (ref "SW2") (pin "1") (pinfunction "1_1") (pintype "passive"))
    )
    (net (code "88") (name "unconnected-(VIT1-1-PadVIT1)") (class "Default")
      (node (ref "VIT1") (pin "VIT1") (pinfunction "1_VIT1") (pintype "passive"))
    )
    (net (code "89") (name "unconnected-(VIT2-1-PadVIT1)") (class "Default")
      (node (ref "VIT2") (pin "VIT1") (pinfunction "1_VIT1") (pintype "passive"))
    )
    (net (code "90") (name "unconnected-(VIT3-1-PadVIT1)") (class "Default")
      (node (ref "VIT3") (pin "VIT1") (pinfunction "1_VIT1") (pintype "passive"))
    )
    (net (code "91") (name "unconnected-(VIT4-1-PadVIT1)") (class "Default")
      (node (ref "VIT4") (pin "VIT1") (pinfunction "1_VIT1") (pintype "passive"))
    )
  )
)
